# MOSFET_Power_Switch.net
KiCad netlist of a schematic drawn in EAGLE
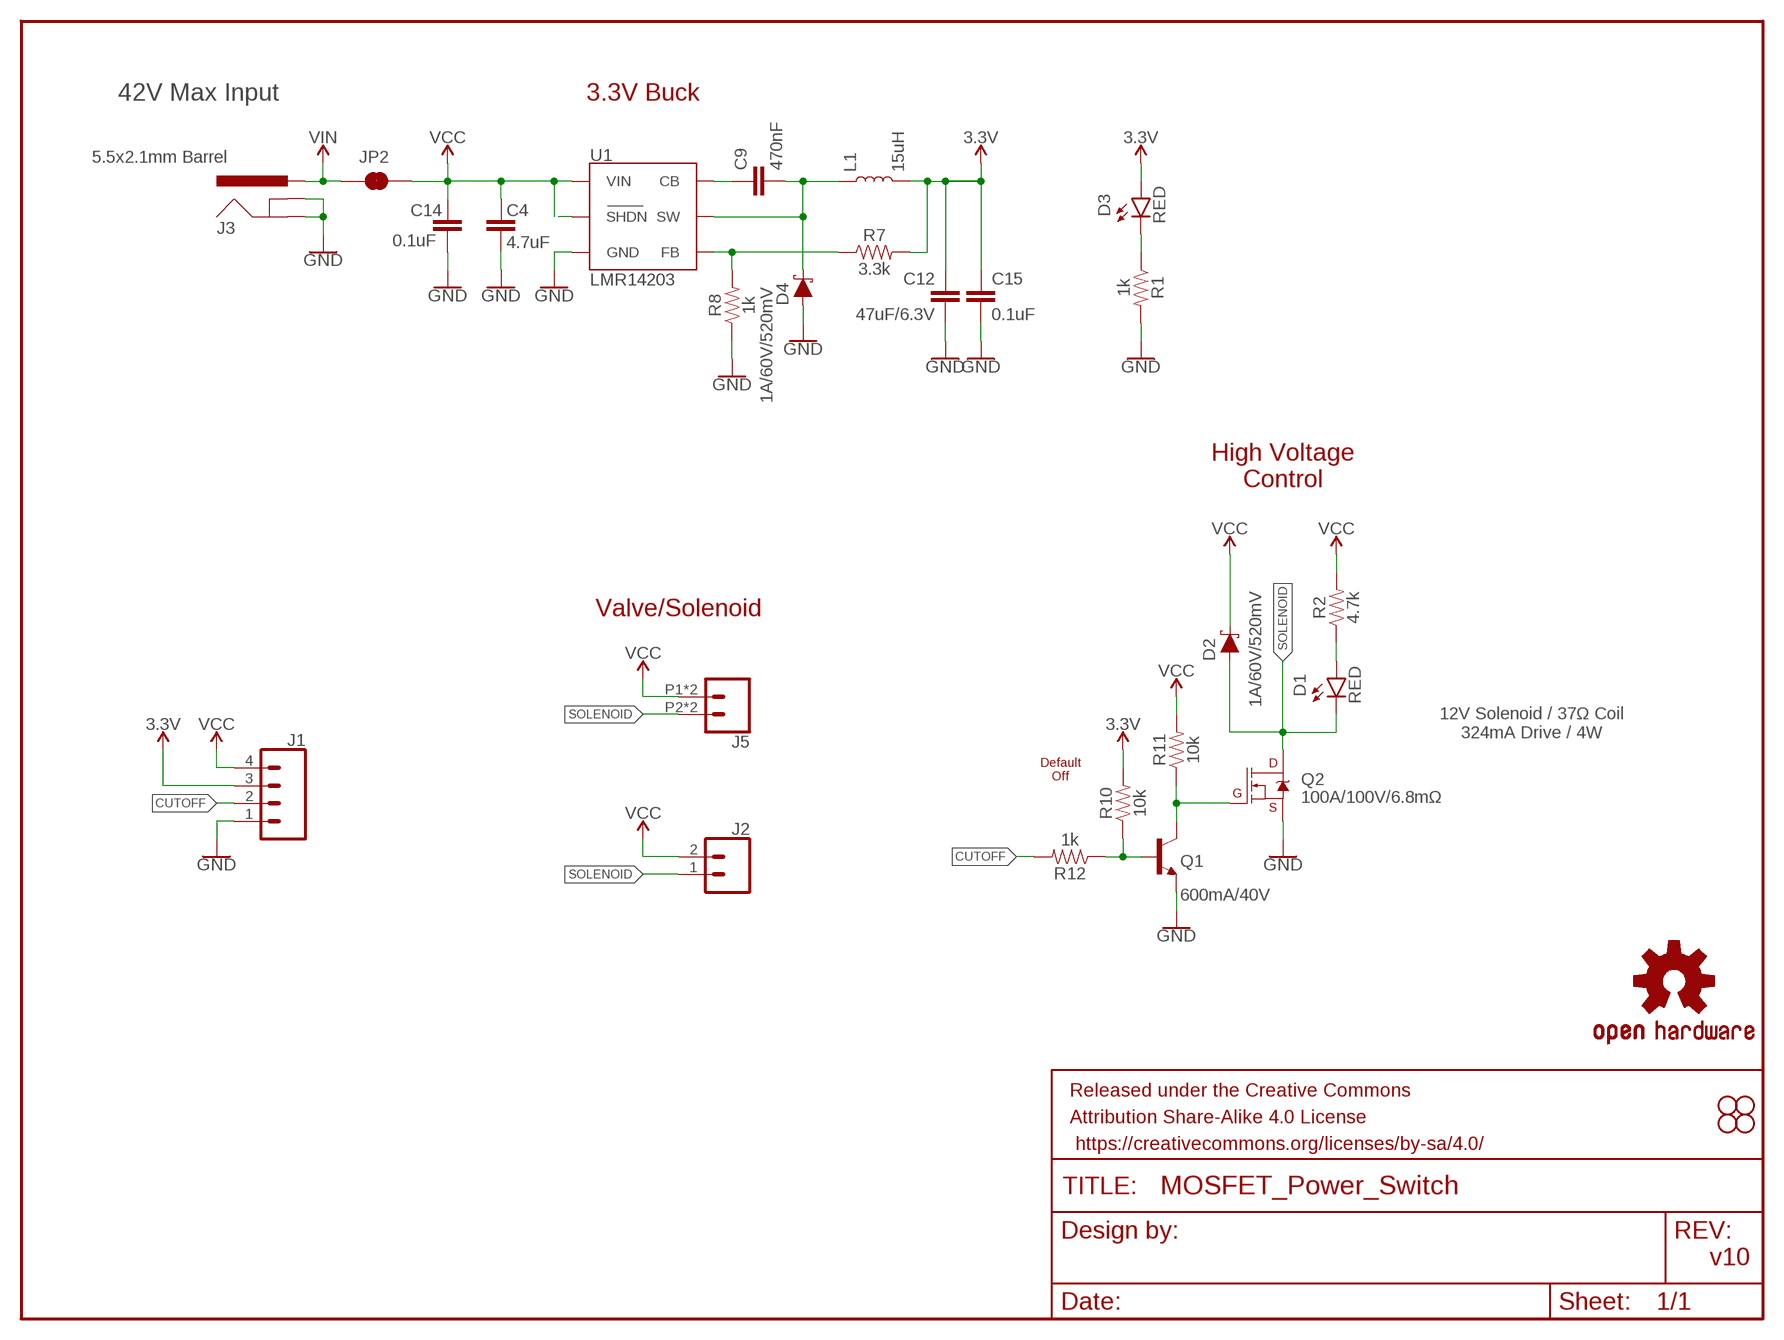
[diagram p0: schematic, sheet 1]

(export (version "E")
  (design (tool "Eeschema 10.0.6"))
  (components
    (comp (ref "C4")
      (value "4.7uF")
      (footprint "eagle-import:0603")
      (libsource (lib "eagle-import") (part "4.7UF-0603-35V-(20%)"))
    )
    (comp (ref "C9")
      (value "470nF")
      (footprint "eagle-import:0603")
      (libsource (lib "eagle-import") (part "470NF-0603-10V-10%-X5R"))
    )
    (comp (ref "C12")
      (value "47uF/6.3V")
      (footprint "eagle-import:0805")
      (libsource (lib "eagle-import") (part "47UF"))
    )
    (comp (ref "C14")
      (value "0.1uF")
      (footprint "eagle-import:0603")
      (libsource (lib "eagle-import") (part "0.1UF-0603-100V-10%"))
    )
    (comp (ref "C15")
      (value "0.1uF")
      (footprint "eagle-import:0603")
      (libsource (lib "eagle-import") (part "0.1UF-0603-25V-(+80/-20%)"))
    )
    (comp (ref "D1")
      (value "RED")
      (footprint "eagle-import:LED-0603")
      (libsource (lib "eagle-import") (part "LED-RED0603"))
    )
    (comp (ref "D2")
      (value "1A/60V/520mV")
      (footprint "eagle-import:DIODE-MICRO-SMP")
      (libsource (lib "eagle-import") (part "DIODE-SCHOTTKY-MSS1P6-M3/89A"))
    )
    (comp (ref "D3")
      (value "RED")
      (footprint "eagle-import:LED-0603")
      (libsource (lib "eagle-import") (part "LED-RED0603"))
    )
    (comp (ref "D4")
      (value "1A/60V/520mV")
      (footprint "eagle-import:DIODE-MICRO-SMP")
      (libsource (lib "eagle-import") (part "DIODE-SCHOTTKY-MSS1P6-M3/89A"))
    )
    (comp (ref "FRAME2")
      (value "FRAME-LETTER")
      (footprint "eagle-import:CREATIVE_COMMONS")
      (libsource (lib "eagle-import") (part "FRAME-LETTER"))
    )
    (comp (ref "H1")
      (value "STAND-OFF")
      (footprint "eagle-import:STAND-OFF")
      (libsource (lib "eagle-import") (part "STAND-OFF"))
    )
    (comp (ref "H2")
      (value "STAND-OFF")
      (footprint "eagle-import:STAND-OFF")
      (libsource (lib "eagle-import") (part "STAND-OFF"))
    )
    (comp (ref "H3")
      (value "STAND-OFF")
      (footprint "eagle-import:STAND-OFF")
      (libsource (lib "eagle-import") (part "STAND-OFF"))
    )
    (comp (ref "H4")
      (value "STAND-OFF")
      (footprint "eagle-import:STAND-OFF")
      (libsource (lib "eagle-import") (part "STAND-OFF"))
    )
    (comp (ref "J1")
      (value "CONN_041X04_NO_SILK_NO_POP")
      (footprint "eagle-import:1X04_NO_SILK")
      (libsource (lib "eagle-import") (part "CONN_041X04_NO_SILK_NO_POP"))
    )
    (comp (ref "J2")
      (value "CONN_021X02_NO_SILK")
      (footprint "eagle-import:1X02_NO_SILK")
      (libsource (lib "eagle-import") (part "CONN_021X02_NO_SILK"))
    )
    (comp (ref "J3")
      (value "5.5x2.1mm Barrel")
      (footprint "eagle-import:POWER_JACK_SMD")
      (libsource (lib "eagle-import") (part "POWER_JACKSMD"))
    )
    (comp (ref "J5")
      (value "CONN_02SMALL_POKEHOME")
      (footprint "eagle-import:1X02_POKEHOME")
      (libsource (lib "eagle-import") (part "CONN_02SMALL_POKEHOME"))
    )
    (comp (ref "JP2")
      (value "JUMPER-COMBO_2_NC_TRACE")
      (footprint "eagle-import:COMBO-JUMPER_2_NC_TRACE")
      (libsource (lib "eagle-import") (part "JUMPER-COMBO_2_NC_TRACE"))
    )
    (comp (ref "L1")
      (value "15uH")
      (footprint "eagle-import:INDUCTOR_LQH32")
      (libsource (lib "eagle-import") (part "INDUCTOR-LHQ32-15UH"))
    )
    (comp (ref "LOGO1")
      (value "OSHW-LOGOS")
      (footprint "eagle-import:OSHW-LOGO-S")
      (libsource (lib "eagle-import") (part "OSHW-LOGOS"))
    )
    (comp (ref "Q1")
      (value "600mA/40V")
      (footprint "eagle-import:SOT23-3")
      (libsource (lib "eagle-import") (part "TRANS_NPN-MMBT2222AL"))
    )
    (comp (ref "Q2")
      (value "100A/100V/6.8mΩ")
      (footprint "eagle-import:TO-263_D2PAK")
      (libsource (lib "eagle-import") (part "MOSFET-NCH-PSMN7R0"))
    )
    (comp (ref "R1")
      (value "1k")
      (footprint "eagle-import:0603")
      (libsource (lib "eagle-import") (part "1KOHM-0603-1/10W-1%"))
    )
    (comp (ref "R2")
      (value "4.7k")
      (footprint "eagle-import:0603")
      (libsource (lib "eagle-import") (part "4.7KOHM-0603-1/10W-1%"))
    )
    (comp (ref "R7")
      (value "3.3k")
      (footprint "eagle-import:0603")
      (libsource (lib "eagle-import") (part "3.3KOHM-0603-1/10W-1%"))
    )
    (comp (ref "R8")
      (value "1k")
      (footprint "eagle-import:0603")
      (libsource (lib "eagle-import") (part "1KOHM-0603-1/10W-1%"))
    )
    (comp (ref "R10")
      (value "10k")
      (footprint "eagle-import:0603")
      (libsource (lib "eagle-import") (part "10KOHM-0603-1/10W-1%"))
    )
    (comp (ref "R11")
      (value "10k")
      (footprint "eagle-import:0603")
      (libsource (lib "eagle-import") (part "10KOHM-0603-1/10W-1%"))
    )
    (comp (ref "R12")
      (value "1k")
      (footprint "eagle-import:0603")
      (libsource (lib "eagle-import") (part "1KOHM-0603-1/10W-1%"))
    )
    (comp (ref "U1")
      (value "LMR14203")
      (footprint "eagle-import:SOT23-6")
      (libsource (lib "eagle-import") (part "LMR14203"))
    )
  )
  (nets
    (net (code "1") (name "3.3V") (class "Default")
      (node (ref "C12") (pin "1") (pinfunction "1_1") (pintype "passive"))
      (node (ref "C15") (pin "1") (pinfunction "1_1") (pintype "passive"))
      (node (ref "D3") (pin "A") (pinfunction "A_A") (pintype "passive"))
      (node (ref "J1") (pin "3") (pinfunction "3_3") (pintype "passive"))
      (node (ref "L1") (pin "P$2") (pinfunction "2_P$2") (pintype "passive"))
      (node (ref "R10") (pin "2") (pinfunction "2_2") (pintype "passive"))
      (node (ref "R7") (pin "2") (pinfunction "2_2") (pintype "passive"))
    )
    (net (code "2") (name "CUTOFF") (class "Default")
      (node (ref "J1") (pin "2") (pinfunction "2_2") (pintype "passive"))
      (node (ref "R12") (pin "2") (pinfunction "2_2") (pintype "passive"))
    )
    (net (code "3") (name "GND") (class "Default")
      (node (ref "C12") (pin "2") (pinfunction "2_2") (pintype "passive"))
      (node (ref "C14") (pin "2") (pinfunction "2_2") (pintype "passive"))
      (node (ref "C15") (pin "2") (pinfunction "2_2") (pintype "passive"))
      (node (ref "C4") (pin "2") (pinfunction "2_2") (pintype "passive"))
      (node (ref "D4") (pin "A") (pinfunction "A_A") (pintype "passive"))
      (node (ref "J1") (pin "1") (pinfunction "1_1") (pintype "passive"))
      (node (ref "J3") (pin "GND") (pinfunction "GNDBREAK_GND") (pintype "bidirectional"))
      (node (ref "J3") (pin "P$4") (pinfunction "GND_P$4") (pintype "bidirectional"))
      (node (ref "Q1") (pin "2") (pinfunction "E_2") (pintype "passive"))
      (node (ref "Q2") (pin "3") (pinfunction "S_3") (pintype "bidirectional"))
      (node (ref "R1") (pin "2") (pinfunction "2_2") (pintype "passive"))
      (node (ref "R8") (pin "1") (pinfunction "1_1") (pintype "passive"))
      (node (ref "U1") (pin "2") (pinfunction "GND_2") (pintype "power_in"))
    )
    (net (code "4") (name "Net-(D1-PadA)") (class "Default")
      (node (ref "D1") (pin "A") (pinfunction "A_A") (pintype "passive"))
      (node (ref "R2") (pin "1") (pinfunction "1_1") (pintype "passive"))
    )
    (net (code "5") (name "Net-(D3-PadC)") (class "Default")
      (node (ref "D3") (pin "C") (pinfunction "C_C") (pintype "passive"))
      (node (ref "R1") (pin "1") (pinfunction "1_1") (pintype "passive"))
    )
    (net (code "6") (name "Net-(L1-1)") (class "Default")
      (node (ref "C9") (pin "2") (pinfunction "2_2") (pintype "passive"))
      (node (ref "D4") (pin "C") (pinfunction "C_C") (pintype "passive"))
      (node (ref "L1") (pin "P$1") (pinfunction "1_P$1") (pintype "passive"))
      (node (ref "U1") (pin "6") (pinfunction "SW_6") (pintype "power_in"))
    )
    (net (code "7") (name "Net-(Q1-B)") (class "Default")
      (node (ref "Q1") (pin "1") (pinfunction "B_1") (pintype "passive"))
      (node (ref "R10") (pin "1") (pinfunction "1_1") (pintype "passive"))
      (node (ref "R12") (pin "1") (pinfunction "1_1") (pintype "passive"))
    )
    (net (code "8") (name "Net-(Q1-C)") (class "Default")
      (node (ref "Q1") (pin "3") (pinfunction "C_3") (pintype "passive"))
      (node (ref "Q2") (pin "1") (pinfunction "G_1") (pintype "bidirectional"))
      (node (ref "R11") (pin "1") (pinfunction "1_1") (pintype "passive"))
    )
    (net (code "9") (name "Net-(U1-CB)") (class "Default")
      (node (ref "C9") (pin "1") (pinfunction "1_1") (pintype "passive"))
      (node (ref "U1") (pin "1") (pinfunction "CB_1") (pintype "input"))
    )
    (net (code "10") (name "Net-(U1-FB)") (class "Default")
      (node (ref "R7") (pin "1") (pinfunction "1_1") (pintype "passive"))
      (node (ref "R8") (pin "2") (pinfunction "2_2") (pintype "passive"))
      (node (ref "U1") (pin "3") (pinfunction "FB_3") (pintype "input"))
    )
    (net (code "11") (name "SOLENOID") (class "Default")
      (node (ref "D1") (pin "C") (pinfunction "C_C") (pintype "passive"))
      (node (ref "D2") (pin "A") (pinfunction "A_A") (pintype "passive"))
      (node (ref "J2") (pin "1") (pinfunction "1_1") (pintype "passive"))
      (node (ref "J5") (pin "P2") (pinfunction "2_P2") (pintype "passive"))
      (node (ref "J5") (pin "P4") (pinfunction "2_P4") (pintype "passive"))
      (node (ref "Q2") (pin "2") (pinfunction "D_2") (pintype "bidirectional"))
    )
    (net (code "12") (name "VCC") (class "Default")
      (node (ref "C14") (pin "1") (pinfunction "1_1") (pintype "passive"))
      (node (ref "C4") (pin "1") (pinfunction "1_1") (pintype "passive"))
      (node (ref "D2") (pin "C") (pinfunction "C_C") (pintype "passive"))
      (node (ref "J1") (pin "4") (pinfunction "4_4") (pintype "passive"))
      (node (ref "J2") (pin "2") (pinfunction "2_2") (pintype "passive"))
      (node (ref "J5") (pin "P1") (pinfunction "1_P1") (pintype "passive"))
      (node (ref "J5") (pin "P3") (pinfunction "1_P3") (pintype "passive"))
      (node (ref "JP2") (pin "2") (pinfunction "2_2") (pintype "passive"))
      (node (ref "JP2") (pin "4") (pinfunction "2_4") (pintype "passive"))
      (node (ref "R11") (pin "2") (pinfunction "2_2") (pintype "passive"))
      (node (ref "R2") (pin "2") (pinfunction "2_2") (pintype "passive"))
      (node (ref "U1") (pin "4") (pinfunction "SHDN_4") (pintype "input"))
      (node (ref "U1") (pin "5") (pinfunction "VIN_5") (pintype "power_in"))
    )
    (net (code "13") (name "VIN") (class "Default")
      (node (ref "J3") (pin "VIN0") (pinfunction "PWR_VIN0") (pintype "bidirectional"))
      (node (ref "JP2") (pin "1") (pinfunction "1_1") (pintype "passive"))
      (node (ref "JP2") (pin "3") (pinfunction "1_3") (pintype "passive"))
    )
  )
)
